# SCH_NFC-Card-Adam_2024-10-10.net
KiCad netlist of a schematic drawn in EasyEDA
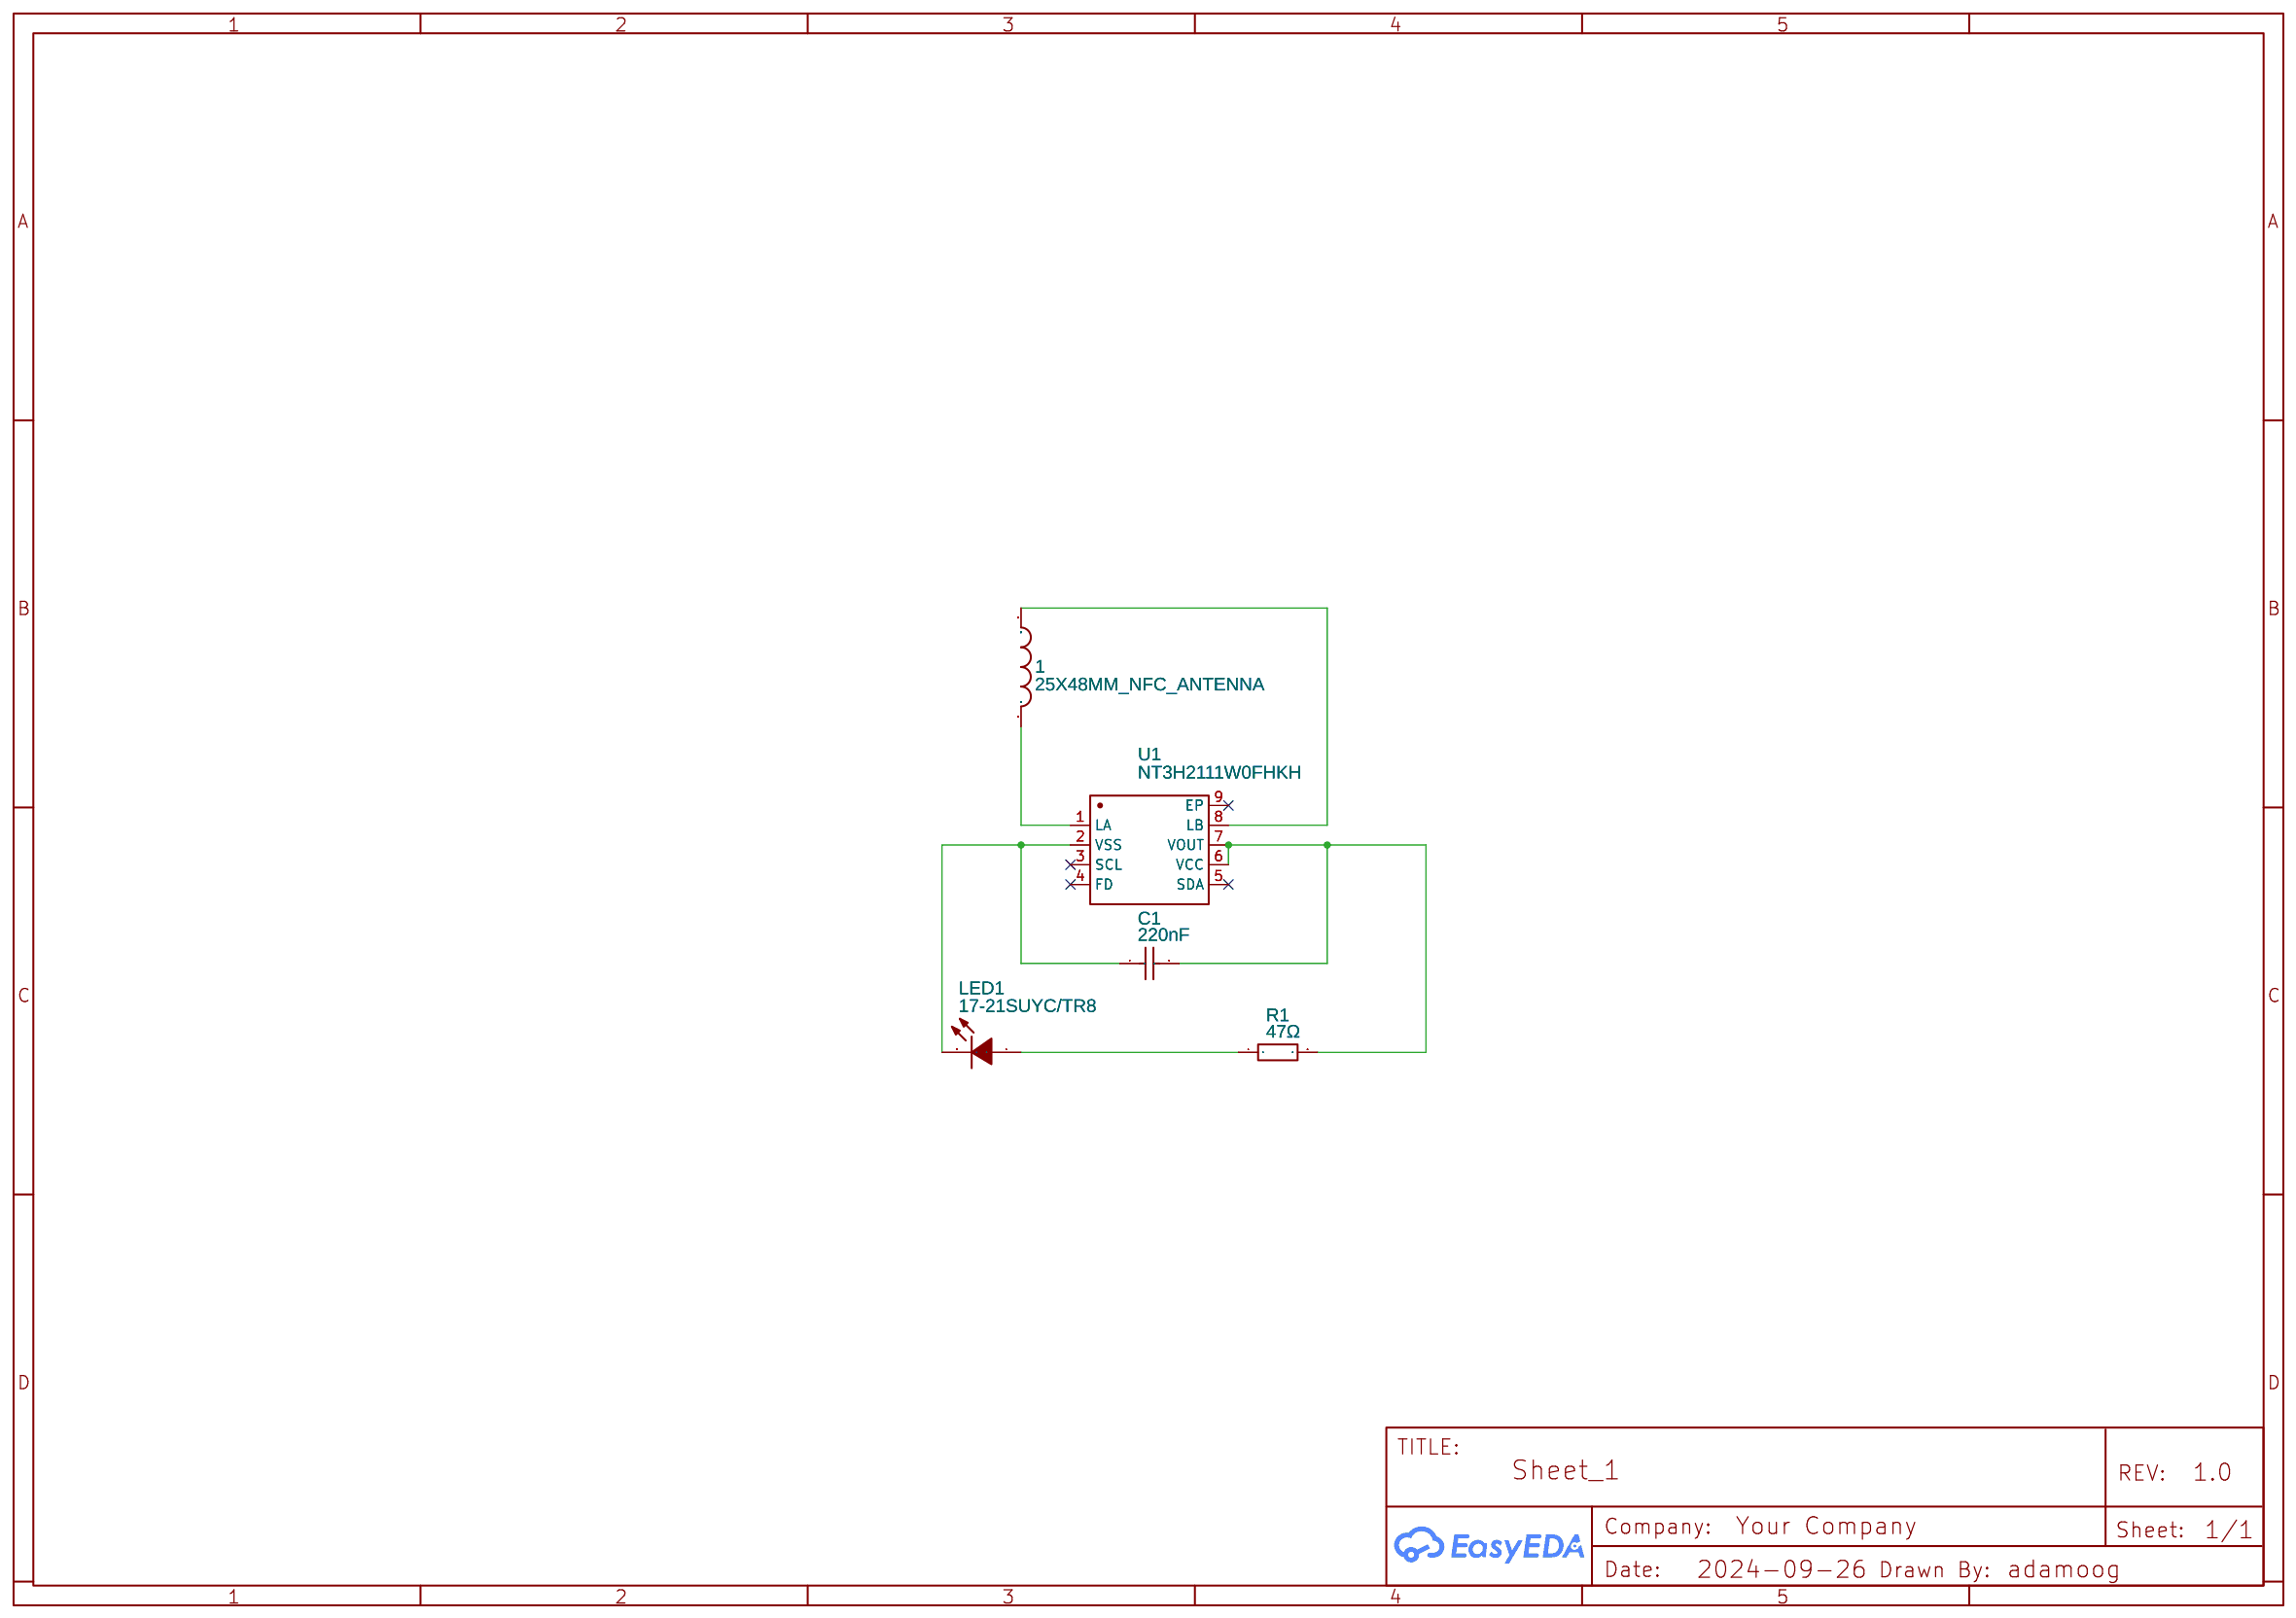
[diagram p0: schematic sheet]

(export (version "E")
  (design (tool "Eeschema 10.0.6"))
  (components
    (comp (ref "1") (value "25X48MM_NFC_ANTENNA") (libsource (lib "") (part "25X48MM_NFC_ANTENNA")))
    (comp (ref "C1")
      (value "220nF")
      (fields
        (field (name "Manufacturer Part") "CL10B224KA8NNNC")
        (field (name "Manufacturer") "SAMSUNG(三星)")
      )
      (libsource (lib "") (part "CL10B224KA8NNNC"))
    )
    (comp (ref "LED1")
      (value "17-21SUYC/TR8")
      (fields (field (name "Manufacturer Part") "KT-0805黄灯") (field (name "Manufacturer") "KENTO"))
      (libsource (lib "") (part "17-21SUYC/TR8"))
    )
    (comp (ref "R1")
      (value "47Ω")
      (fields
        (field (name "Manufacturer Part") "0603WAF470JT5E")
        (field (name "Manufacturer") "UNI-ROYAL(厚声)")
      )
      (libsource (lib "") (part "0603WAF470JT5E"))
    )
    (comp (ref "U1")
      (value "NT3H2111W0FHKH")
      (fields (field (name "Manufacturer") "NXP(恩智浦)"))
      (libsource (lib "") (part "NT3H2111W0FHKH"))
    )
  )
  (nets
    (net (code "1") (name "Net-(LED1-+)") (class "Default")
      (node (ref "LED1") (pin "1") (pinfunction "+_1") (pintype "unspecified"))
      (node (ref "R1") (pin "1") (pinfunction "1_1") (pintype "input"))
    )
    (net (code "2") (name "Net-(LED1--)") (class "Default")
      (node (ref "C1") (pin "1") (pinfunction "1_1") (pintype "input"))
      (node (ref "LED1") (pin "2") (pinfunction "-_2") (pintype "unspecified"))
      (node (ref "U1") (pin "2") (pinfunction "VSS_2") (pintype "unspecified"))
    )
    (net (code "3") (name "Net-(U1-LA)") (class "Default")
      (node (ref "1") (pin "P$2") (pinfunction "P$2_P$2") (pintype "bidirectional"))
      (node (ref "U1") (pin "1") (pinfunction "LA_1") (pintype "unspecified"))
    )
    (net (code "4") (name "Net-(U1-LB)") (class "Default")
      (node (ref "1") (pin "P$1") (pinfunction "P$1_P$1") (pintype "bidirectional"))
      (node (ref "U1") (pin "8") (pinfunction "LB_8") (pintype "unspecified"))
    )
    (net (code "5") (name "Net-(U1-VCC)") (class "Default")
      (node (ref "C1") (pin "2") (pinfunction "2_2") (pintype "input"))
      (node (ref "R1") (pin "2") (pinfunction "2_2") (pintype "input"))
      (node (ref "U1") (pin "6") (pinfunction "VCC_6") (pintype "unspecified"))
      (node (ref "U1") (pin "7") (pinfunction "VOUT_7") (pintype "unspecified"))
    )
    (net (code "6") (name "unconnected-(U1-EP-Pad9)") (class "Default")
      (node (ref "U1") (pin "9") (pinfunction "EP_9") (pintype "unspecified+no_connect"))
    )
    (net (code "7") (name "unconnected-(U1-FD-Pad4)") (class "Default")
      (node (ref "U1") (pin "4") (pinfunction "FD_4") (pintype "unspecified+no_connect"))
    )
    (net (code "8") (name "unconnected-(U1-SCL-Pad3)") (class "Default")
      (node (ref "U1") (pin "3") (pinfunction "SCL_3") (pintype "unspecified+no_connect"))
    )
    (net (code "9") (name "unconnected-(U1-SDA-Pad5)") (class "Default")
      (node (ref "U1") (pin "5") (pinfunction "SDA_5") (pintype "unspecified+no_connect"))
    )
  )
)
